# TopLevel.net
KiCad netlist of a schematic drawn in Altium Designer
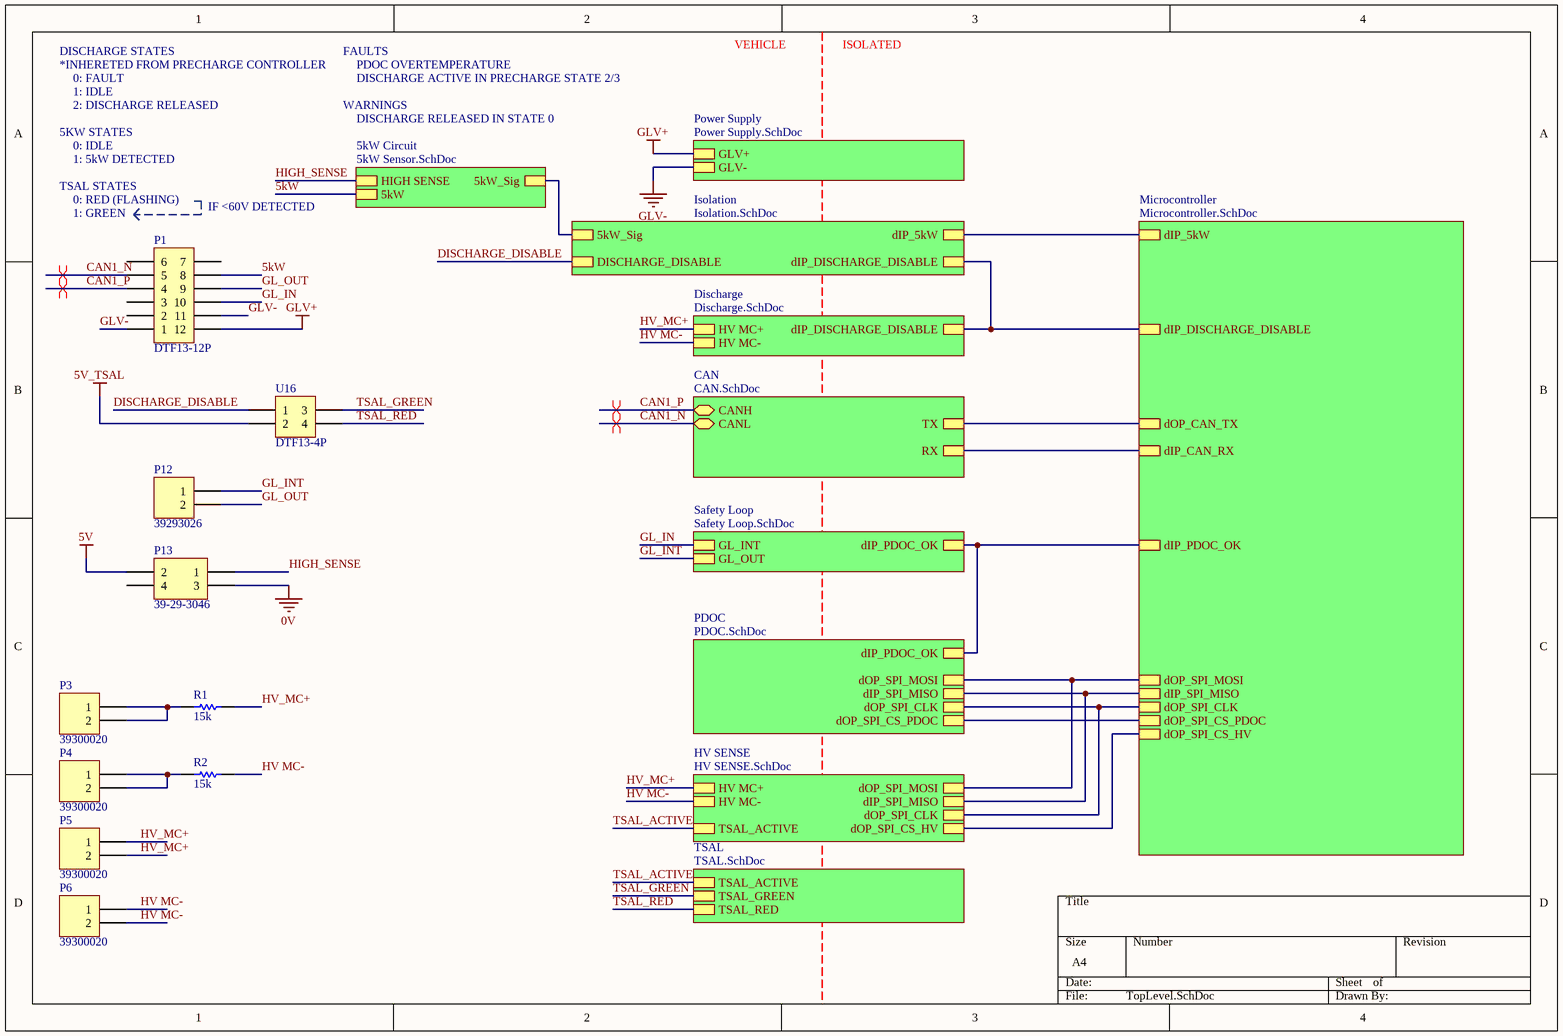
[diagram p0: TopLevel.SchDoc]

(export (version "E")
  (design (tool "Eeschema 10.0.6"))
  (components
    (comp (ref "P1")
      (value "DTF13-12P")
      (footprint "DTF13-12P")
      (fields (field (name "DIGIKEY PART NUMBER") "1734-1861-ND") (field (name "CONTACT") "Copper Alloy"))
      (libsource (lib "ts_standard_connectors") (part "DT13-12P"))
    )
    (comp (ref "P3")
      (value "39300020")
      (footprint "39300020")
      (fields (field (name "DIGIKEY PART NUMBER") "WM21351-ND") (field (name "CONTACT") "Tin"))
      (libsource (lib "ts_standard_connectors") (part "2"))
    )
    (comp (ref "P4")
      (value "39300020")
      (footprint "39300020")
      (fields (field (name "DIGIKEY PART NUMBER") "WM21351-ND") (field (name "CONTACT") "Tin"))
      (libsource (lib "ts_standard_connectors") (part "2"))
    )
    (comp (ref "P5")
      (value "39300020")
      (footprint "39300020")
      (fields (field (name "DIGIKEY PART NUMBER") "WM21351-ND") (field (name "CONTACT") "Tin"))
      (libsource (lib "ts_standard_connectors") (part "2"))
    )
    (comp (ref "P6")
      (value "39300020")
      (footprint "39300020")
      (fields (field (name "DIGIKEY PART NUMBER") "WM21351-ND") (field (name "CONTACT") "Tin"))
      (libsource (lib "ts_standard_connectors") (part "2"))
    )
    (comp (ref "P12")
      (value "39293026")
      (footprint "39293026")
      (fields (field (name "DIGIKEY PART NUMBER") "WM3843-ND") (field (name "CONTACT") "Tin"))
      (libsource (lib "ts_standard_connectors") (part "2"))
    )
    (comp (ref "P13")
      (value "39-29-3046")
      (footprint "39-29-3046-Footprint-1")
      (description "Rectangular Power Connector, 4 Contact(s), Male, Solder Terminal, Plug")
      (libsource (lib "Team Swinburne") (part "39-29-3046"))
    )
    (comp (ref "R1")
      (value "15k")
      (footprint "TE_SMF7")
      (fields
        (field (name "PART NUMBER") "SMF715KJ")
        (field (name "MANUFACTURER") "TE")
        (field (name "TOLERANCE") "0.05")
      )
      (libsource (lib "ts_standard_library") (part "Resistor"))
    )
    (comp (ref "R2")
      (value "15k")
      (footprint "TE_SMF7")
      (fields
        (field (name "PART NUMBER") "SMF715KJ")
        (field (name "MANUFACTURER") "TE")
        (field (name "TOLERANCE") "0.05")
      )
      (libsource (lib "ts_standard_library") (part "Resistor"))
    )
    (comp (ref "U16")
      (value "DTF13-4P")
      (footprint "DTF13-4P")
      (fields (field (name "DIGIKEY PART NUMBER") "1734-1646-ND") (field (name "CONTACT") "Copper Alloy"))
      (libsource (lib "ts_standard_connectors") (part "DT13-4P"))
    )
  )
  (nets
    (net (code "1") (name "/5kW") (class "Default")
      (node (ref "P1") (pin "8") (pinfunction "8_8") (pintype "passive"))
    )
    (net (code "3") (name "/CAN1_N") (class "Default")
      (node (ref "P1") (pin "5") (pinfunction "5_5") (pintype "power_in"))
    )
    (net (code "4") (name "/CAN1_P") (class "Default")
      (node (ref "P1") (pin "4") (pinfunction "4_4") (pintype "power_in"))
    )
    (net (code "5") (name "/DISCHARGE_DISABLE") (class "Default")
      (node (ref "U16") (pin "1") (pinfunction "1_1") (pintype "power_in"))
    )
    (net (code "6") (name "/GL_IN") (class "Default")
      (node (ref "P1") (pin "10") (pinfunction "10_10") (pintype "passive"))
    )
    (net (code "7") (name "/GL_INT") (class "Default")
      (node (ref "P12") (pin "1") (pinfunction "1_1") (pintype "passive"))
    )
    (net (code "8") (name "/GL_OUT") (class "Default")
      (node (ref "P1") (pin "9") (pinfunction "9_9") (pintype "passive"))
      (node (ref "P12") (pin "2") (pinfunction "2_2") (pintype "passive"))
    )
    (net (code "9") (name "/HIGH_SENSE") (class "Default")
      (node (ref "P13") (pin "1") (pinfunction "1_1") (pintype "passive"))
    )
    (net (code "10") (name "/HV MC-") (class "Default")
      (node (ref "P6") (pin "1") (pinfunction "1_1") (pintype "passive"))
      (node (ref "P6") (pin "2") (pinfunction "2_2") (pintype "passive"))
      (node (ref "R2") (pin "2") (pinfunction "2_2") (pintype "passive"))
    )
    (net (code "11") (name "/HV_MC+") (class "Default")
      (node (ref "P5") (pin "1") (pinfunction "1_1") (pintype "passive"))
      (node (ref "P5") (pin "2") (pinfunction "2_2") (pintype "passive"))
      (node (ref "R1") (pin "2") (pinfunction "2_2") (pintype "passive"))
    )
    (net (code "14") (name "/TSAL_GREEN") (class "Default")
      (node (ref "U16") (pin "3") (pinfunction "3_3") (pintype "passive"))
    )
    (net (code "15") (name "/TSAL_RED") (class "Default")
      (node (ref "U16") (pin "4") (pinfunction "4_4") (pintype "passive"))
    )
    (net (code "25") (name "0V") (class "Default")
      (node (ref "P13") (pin "3") (pinfunction "3_3") (pintype "passive"))
    )
    (net (code "26") (name "5V") (class "Default")
      (node (ref "P13") (pin "2") (pinfunction "2_2") (pintype "passive"))
    )
    (net (code "27") (name "5V_TSAL") (class "Default")
      (node (ref "U16") (pin "2") (pinfunction "2_2") (pintype "power_in"))
    )
    (net (code "28") (name "GLV+") (class "Default")
      (node (ref "P1") (pin "12") (pinfunction "12_12") (pintype "passive"))
    )
    (net (code "29") (name "GLV-") (class "Default")
      (node (ref "P1") (pin "1") (pinfunction "1_1") (pintype "power_in"))
      (node (ref "P1") (pin "11") (pinfunction "11_11") (pintype "passive"))
    )
    (net (code "30") (name "Net-(P3-Pad1)") (class "Default")
      (node (ref "P3") (pin "1") (pinfunction "1_1") (pintype "passive"))
      (node (ref "P3") (pin "2") (pinfunction "2_2") (pintype "passive"))
      (node (ref "R1") (pin "1") (pinfunction "1_1") (pintype "passive"))
    )
    (net (code "31") (name "Net-(P4-Pad1)") (class "Default")
      (node (ref "P4") (pin "1") (pinfunction "1_1") (pintype "passive"))
      (node (ref "P4") (pin "2") (pinfunction "2_2") (pintype "passive"))
      (node (ref "R2") (pin "1") (pinfunction "1_1") (pintype "passive"))
    )
    (net (code "32") (name "unconnected-(P1-Pad2)") (class "Default")
      (node (ref "P1") (pin "2") (pinfunction "2_2") (pintype "power_in"))
    )
    (net (code "33") (name "unconnected-(P1-Pad3)") (class "Default")
      (node (ref "P1") (pin "3") (pinfunction "3_3") (pintype "power_in"))
    )
    (net (code "34") (name "unconnected-(P1-Pad6)") (class "Default")
      (node (ref "P1") (pin "6") (pinfunction "6_6") (pintype "power_in"))
    )
    (net (code "35") (name "unconnected-(P1-Pad7)") (class "Default")
      (node (ref "P1") (pin "7") (pinfunction "7_7") (pintype "passive"))
    )
    (net (code "36") (name "unconnected-(P13-Pad4)") (class "Default")
      (node (ref "P13") (pin "4") (pinfunction "4_4") (pintype "passive"))
    )
  )
)
